# com.net
KiCad netlist of a schematic drawn in Altium Designer
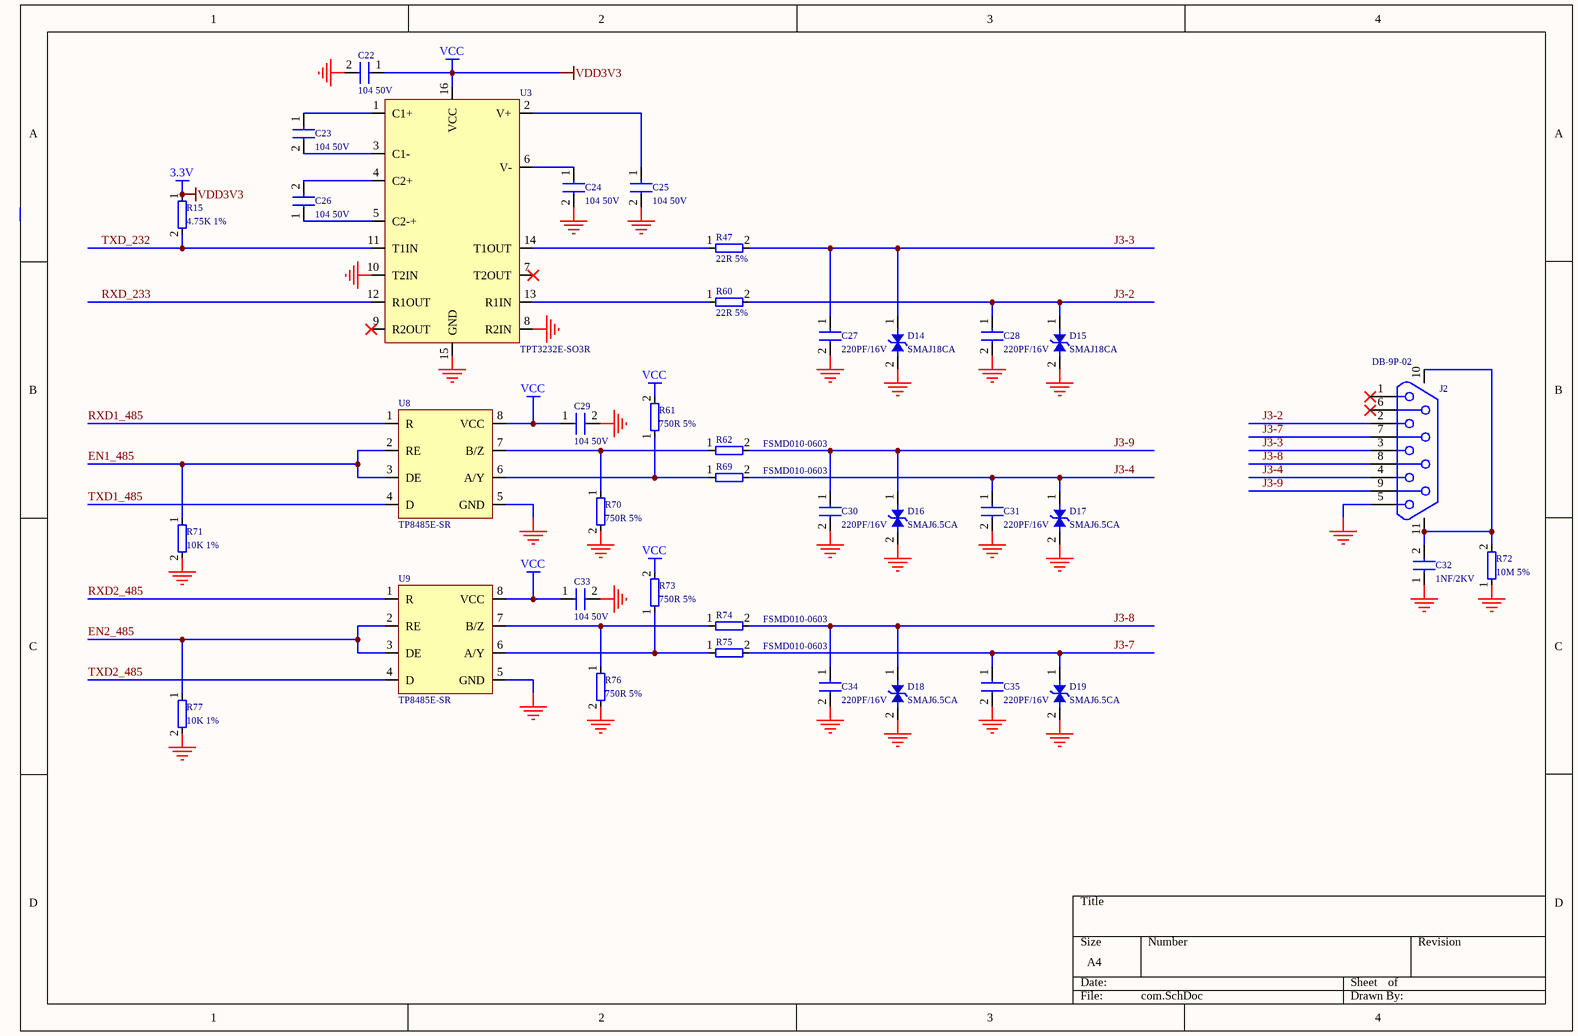
[diagram p0: com.SchDoc]

(export (version "E")
  (design (tool "Eeschema 10.0.6"))
  (components
    (comp (ref "C22") (value "104 50V") (footprint "0603C") (libsource (lib "*") (part "CAP")))
    (comp (ref "C23") (value "104 50V") (footprint "0603C") (libsource (lib "*") (part "CAP")))
    (comp (ref "C24") (value "104 50V") (footprint "0603C") (libsource (lib "*") (part "CAP")))
    (comp (ref "C25") (value "104 50V") (footprint "0603C") (libsource (lib "*") (part "CAP")))
    (comp (ref "C26") (value "104 50V") (footprint "0603C") (libsource (lib "*") (part "CAP")))
    (comp (ref "C27") (value "220PF/16V") (footprint "0603C") (libsource (lib "*") (part "CAP")))
    (comp (ref "C28") (value "220PF/16V") (footprint "0603C") (libsource (lib "*") (part "CAP")))
    (comp (ref "C29") (value "104 50V") (footprint "0603C") (libsource (lib "*") (part "CAP")))
    (comp (ref "C30") (value "220PF/16V") (footprint "0603C") (libsource (lib "*") (part "CAP")))
    (comp (ref "C31") (value "220PF/16V") (footprint "0603C") (libsource (lib "*") (part "CAP")))
    (comp (ref "C32") (value "1NF/2KV") (footprint "1206C") (libsource (lib "*") (part "CAP")))
    (comp (ref "C33") (value "104 50V") (footprint "0603C") (libsource (lib "*") (part "CAP")))
    (comp (ref "C34") (value "220PF/16V") (footprint "0603C") (libsource (lib "*") (part "CAP")))
    (comp (ref "C35") (value "220PF/16V") (footprint "0603C") (libsource (lib "*") (part "CAP")))
    (comp (ref "D14") (value "SMAJ18CA") (footprint "SMA") (libsource (lib "*") (part "D_ESD")))
    (comp (ref "D15") (value "SMAJ18CA") (footprint "SMA") (libsource (lib "*") (part "D_ESD")))
    (comp (ref "D16") (value "SMAJ6.5CA") (footprint "SMA") (libsource (lib "*") (part "D_ESD")))
    (comp (ref "D17") (value "SMAJ6.5CA") (footprint "SMA") (libsource (lib "*") (part "D_ESD")))
    (comp (ref "D18") (value "SMAJ6.5CA") (footprint "SMA") (libsource (lib "*") (part "D_ESD")))
    (comp (ref "D19") (value "SMAJ6.5CA") (footprint "SMA") (libsource (lib "*") (part "D_ESD")))
    (comp (ref "J2") (value "DB-9P-02") (footprint "DIP-9") (libsource (lib "*") (part "DB9")))
    (comp (ref "R15") (value "4.75K 1%") (footprint "0603R") (libsource (lib "*") (part "RES")))
    (comp (ref "R47") (value "22R 5%") (footprint "0603R") (libsource (lib "*") (part "RES")))
    (comp (ref "R60") (value "22R 5%") (footprint "0603R") (libsource (lib "*") (part "RES")))
    (comp (ref "R61") (value "750R 5%") (footprint "0603R") (libsource (lib "*") (part "RES")))
    (comp (ref "R62") (value "FSMD010-0603") (footprint "0603R") (libsource (lib "*") (part "RES")))
    (comp (ref "R69") (value "FSMD010-0603") (footprint "0603R") (libsource (lib "*") (part "RES")))
    (comp (ref "R70") (value "750R 5%") (footprint "0603R") (libsource (lib "*") (part "RES")))
    (comp (ref "R71") (value "10K 1%") (footprint "0603R") (libsource (lib "*") (part "RES")))
    (comp (ref "R72") (value "10M 5%") (footprint "1206r") (libsource (lib "*") (part "RES")))
    (comp (ref "R73") (value "750R 5%") (footprint "0603R") (libsource (lib "*") (part "RES")))
    (comp (ref "R74") (value "FSMD010-0603") (footprint "0603R") (libsource (lib "*") (part "RES")))
    (comp (ref "R75") (value "FSMD010-0603") (footprint "0603R") (libsource (lib "*") (part "RES")))
    (comp (ref "R76") (value "750R 5%") (footprint "0603R") (libsource (lib "*") (part "RES")))
    (comp (ref "R77") (value "10K 1%") (footprint "0603R") (libsource (lib "*") (part "RES")))
    (comp (ref "U3")
      (value "TPT3232E-SO3R")
      (footprint "SO-16Z")
      (libsource (lib "*") (part "TPT3232E-SO3R"))
    )
    (comp (ref "U8") (value "TP8485E-SR") (footprint "SO-8") (libsource (lib "*") (part "TP8485E-SR")))
    (comp (ref "U9") (value "TP8485E-SR") (footprint "SO-8") (libsource (lib "*") (part "TP8485E-SR")))
  )
  (nets
    (net (code "1") (name "/EN1_485") (class "Default")
      (node (ref "R71") (pin "1") (pinfunction "1_1") (pintype "passive"))
      (node (ref "U8") (pin "2") (pinfunction "RE_2") (pintype "passive"))
      (node (ref "U8") (pin "3") (pinfunction "DE_3") (pintype "passive"))
    )
    (net (code "2") (name "/EN2_485") (class "Default")
      (node (ref "R77") (pin "1") (pinfunction "1_1") (pintype "passive"))
      (node (ref "U9") (pin "2") (pinfunction "RE_2") (pintype "passive"))
      (node (ref "U9") (pin "3") (pinfunction "DE_3") (pintype "passive"))
    )
    (net (code "3") (name "/J3-2") (class "Default")
      (node (ref "C28") (pin "1") (pintype "passive"))
      (node (ref "D15") (pin "1") (pintype "passive"))
      (node (ref "J2") (pin "2") (pinfunction "2_2") (pintype "passive"))
      (node (ref "R60") (pin "2") (pinfunction "2_2") (pintype "passive"))
    )
    (net (code "4") (name "/J3-3") (class "Default")
      (node (ref "C27") (pin "1") (pintype "passive"))
      (node (ref "D14") (pin "1") (pintype "passive"))
      (node (ref "J2") (pin "3") (pinfunction "3_3") (pintype "passive"))
      (node (ref "R47") (pin "2") (pinfunction "2_2") (pintype "passive"))
    )
    (net (code "5") (name "/J3-4") (class "Default")
      (node (ref "C31") (pin "1") (pintype "passive"))
      (node (ref "D17") (pin "1") (pintype "passive"))
      (node (ref "J2") (pin "4") (pinfunction "4_4") (pintype "passive"))
      (node (ref "R69") (pin "2") (pinfunction "2_2") (pintype "passive"))
    )
    (net (code "6") (name "/J3-7") (class "Default")
      (node (ref "C35") (pin "1") (pintype "passive"))
      (node (ref "D19") (pin "1") (pintype "passive"))
      (node (ref "J2") (pin "7") (pinfunction "7_7") (pintype "passive"))
      (node (ref "R75") (pin "2") (pinfunction "2_2") (pintype "passive"))
    )
    (net (code "7") (name "/J3-8") (class "Default")
      (node (ref "C34") (pin "1") (pintype "passive"))
      (node (ref "D18") (pin "1") (pintype "passive"))
      (node (ref "J2") (pin "8") (pinfunction "8_8") (pintype "passive"))
      (node (ref "R74") (pin "2") (pinfunction "2_2") (pintype "passive"))
    )
    (net (code "8") (name "/J3-9") (class "Default")
      (node (ref "C30") (pin "1") (pintype "passive"))
      (node (ref "D16") (pin "1") (pintype "passive"))
      (node (ref "J2") (pin "9") (pinfunction "9_9") (pintype "passive"))
      (node (ref "R62") (pin "2") (pinfunction "2_2") (pintype "passive"))
    )
    (net (code "9") (name "/RXD1_485") (class "Default")
      (node (ref "U8") (pin "1") (pinfunction "R_1") (pintype "passive"))
    )
    (net (code "10") (name "/RXD2_485") (class "Default")
      (node (ref "U9") (pin "1") (pinfunction "R_1") (pintype "passive"))
    )
    (net (code "11") (name "/RXD_233") (class "Default")
      (node (ref "U3") (pin "12") (pinfunction "R1OUT_12") (pintype "passive"))
    )
    (net (code "12") (name "/TXD1_485") (class "Default")
      (node (ref "U8") (pin "4") (pinfunction "D_4") (pintype "passive"))
    )
    (net (code "13") (name "/TXD2_485") (class "Default")
      (node (ref "U9") (pin "4") (pinfunction "D_4") (pintype "passive"))
    )
    (net (code "14") (name "/TXD_232") (class "Default")
      (node (ref "R15") (pin "2") (pinfunction "2_2") (pintype "passive"))
      (node (ref "U3") (pin "11") (pinfunction "T1IN_11") (pintype "passive"))
    )
    (net (code "15") (name "3.3V") (class "Default")
      (node (ref "C22") (pin "1") (pintype "passive"))
      (node (ref "C29") (pin "1") (pintype "passive"))
      (node (ref "C33") (pin "1") (pintype "passive"))
      (node (ref "R15") (pin "1") (pinfunction "1_1") (pintype "passive"))
      (node (ref "R61") (pin "2") (pinfunction "2_2") (pintype "passive"))
      (node (ref "R73") (pin "2") (pinfunction "2_2") (pintype "passive"))
      (node (ref "U3") (pin "16") (pinfunction "VCC_16") (pintype "passive"))
      (node (ref "U8") (pin "8") (pinfunction "VCC_8") (pintype "passive"))
      (node (ref "U9") (pin "8") (pinfunction "VCC_8") (pintype "passive"))
    )
    (net (code "16") (name "GND") (class "Default")
      (node (ref "C22") (pin "2") (pintype "passive"))
      (node (ref "C24") (pin "2") (pintype "passive"))
      (node (ref "C25") (pin "2") (pintype "passive"))
      (node (ref "C27") (pin "2") (pintype "passive"))
      (node (ref "C28") (pin "2") (pintype "passive"))
      (node (ref "C29") (pin "2") (pintype "passive"))
      (node (ref "C30") (pin "2") (pintype "passive"))
      (node (ref "C31") (pin "2") (pintype "passive"))
      (node (ref "C32") (pin "1") (pintype "passive"))
      (node (ref "C33") (pin "2") (pintype "passive"))
      (node (ref "C34") (pin "2") (pintype "passive"))
      (node (ref "C35") (pin "2") (pintype "passive"))
      (node (ref "D14") (pin "2") (pintype "passive"))
      (node (ref "D15") (pin "2") (pintype "passive"))
      (node (ref "D16") (pin "2") (pintype "passive"))
      (node (ref "D17") (pin "2") (pintype "passive"))
      (node (ref "D18") (pin "2") (pintype "passive"))
      (node (ref "D19") (pin "2") (pintype "passive"))
      (node (ref "J2") (pin "5") (pinfunction "5_5") (pintype "passive"))
      (node (ref "R70") (pin "2") (pinfunction "2_2") (pintype "passive"))
      (node (ref "R71") (pin "2") (pinfunction "2_2") (pintype "passive"))
      (node (ref "R72") (pin "1") (pinfunction "1_1") (pintype "passive"))
      (node (ref "R76") (pin "2") (pinfunction "2_2") (pintype "passive"))
      (node (ref "R77") (pin "2") (pinfunction "2_2") (pintype "passive"))
      (node (ref "U3") (pin "10") (pinfunction "T2IN_10") (pintype "passive"))
      (node (ref "U3") (pin "15") (pinfunction "GND_15") (pintype "passive"))
      (node (ref "U3") (pin "8") (pinfunction "R2IN_8") (pintype "passive"))
      (node (ref "U8") (pin "5") (pinfunction "GND_5") (pintype "passive"))
      (node (ref "U9") (pin "5") (pinfunction "GND_5") (pintype "passive"))
    )
    (net (code "17") (name "Net-(C32-Pad2)") (class "Default")
      (node (ref "C32") (pin "2") (pintype "passive"))
      (node (ref "J2") (pin "10") (pintype "passive"))
      (node (ref "J2") (pin "11") (pintype "passive"))
      (node (ref "R72") (pin "2") (pinfunction "2_2") (pintype "passive"))
    )
    (net (code "18") (name "Net-(U3-C1+)") (class "Default")
      (node (ref "C23") (pin "1") (pintype "passive"))
      (node (ref "U3") (pin "1") (pinfunction "C1+_1") (pintype "passive"))
    )
    (net (code "19") (name "Net-(U3-C1-)") (class "Default")
      (node (ref "C23") (pin "2") (pintype "passive"))
      (node (ref "U3") (pin "3") (pinfunction "C1-_3") (pintype "passive"))
    )
    (net (code "20") (name "Net-(U3-C2+)") (class "Default")
      (node (ref "C26") (pin "2") (pintype "passive"))
      (node (ref "U3") (pin "4") (pinfunction "C2+_4") (pintype "passive"))
    )
    (net (code "21") (name "Net-(U3-C2-+)") (class "Default")
      (node (ref "C26") (pin "1") (pintype "passive"))
      (node (ref "U3") (pin "5") (pinfunction "C2-+_5") (pintype "passive"))
    )
    (net (code "22") (name "Net-(U3-R1IN)") (class "Default")
      (node (ref "R60") (pin "1") (pinfunction "1_1") (pintype "passive"))
      (node (ref "U3") (pin "13") (pinfunction "R1IN_13") (pintype "passive"))
    )
    (net (code "23") (name "Net-(U3-T1OUT)") (class "Default")
      (node (ref "R47") (pin "1") (pinfunction "1_1") (pintype "passive"))
      (node (ref "U3") (pin "14") (pinfunction "T1OUT_14") (pintype "passive"))
    )
    (net (code "24") (name "Net-(U3-V+)") (class "Default")
      (node (ref "C25") (pin "1") (pintype "passive"))
      (node (ref "U3") (pin "2") (pinfunction "V+_2") (pintype "passive"))
    )
    (net (code "25") (name "Net-(U3-V-)") (class "Default")
      (node (ref "C24") (pin "1") (pintype "passive"))
      (node (ref "U3") (pin "6") (pinfunction "V-_6") (pintype "passive"))
    )
    (net (code "26") (name "Net-(U8-A{slash}Y)") (class "Default")
      (node (ref "R61") (pin "1") (pinfunction "1_1") (pintype "passive"))
      (node (ref "R69") (pin "1") (pinfunction "1_1") (pintype "passive"))
      (node (ref "U8") (pin "6") (pinfunction "A/Y_6") (pintype "passive"))
    )
    (net (code "27") (name "Net-(U8-B{slash}Z)") (class "Default")
      (node (ref "R62") (pin "1") (pinfunction "1_1") (pintype "passive"))
      (node (ref "R70") (pin "1") (pinfunction "1_1") (pintype "passive"))
      (node (ref "U8") (pin "7") (pinfunction "B/Z_7") (pintype "passive"))
    )
    (net (code "28") (name "Net-(U9-A{slash}Y)") (class "Default")
      (node (ref "R73") (pin "1") (pinfunction "1_1") (pintype "passive"))
      (node (ref "R75") (pin "1") (pinfunction "1_1") (pintype "passive"))
      (node (ref "U9") (pin "6") (pinfunction "A/Y_6") (pintype "passive"))
    )
    (net (code "29") (name "Net-(U9-B{slash}Z)") (class "Default")
      (node (ref "R74") (pin "1") (pinfunction "1_1") (pintype "passive"))
      (node (ref "R76") (pin "1") (pinfunction "1_1") (pintype "passive"))
      (node (ref "U9") (pin "7") (pinfunction "B/Z_7") (pintype "passive"))
    )
    (net (code "30") (name "unconnected-(J2-Pad1)") (class "Default")
      (node (ref "J2") (pin "1") (pinfunction "1_1") (pintype "passive+no_connect"))
    )
    (net (code "31") (name "unconnected-(J2-Pad6)") (class "Default")
      (node (ref "J2") (pin "6") (pinfunction "6_6") (pintype "passive+no_connect"))
    )
    (net (code "32") (name "unconnected-(U3-R2OUT-Pad9)") (class "Default")
      (node (ref "U3") (pin "9") (pinfunction "R2OUT_9") (pintype "passive+no_connect"))
    )
    (net (code "33") (name "unconnected-(U3-T2OUT-Pad7)") (class "Default")
      (node (ref "U3") (pin "7") (pinfunction "T2OUT_7") (pintype "passive+no_connect"))
    )
  )
)
